# tsal.net
KiCad netlist of a schematic drawn in Altium Designer
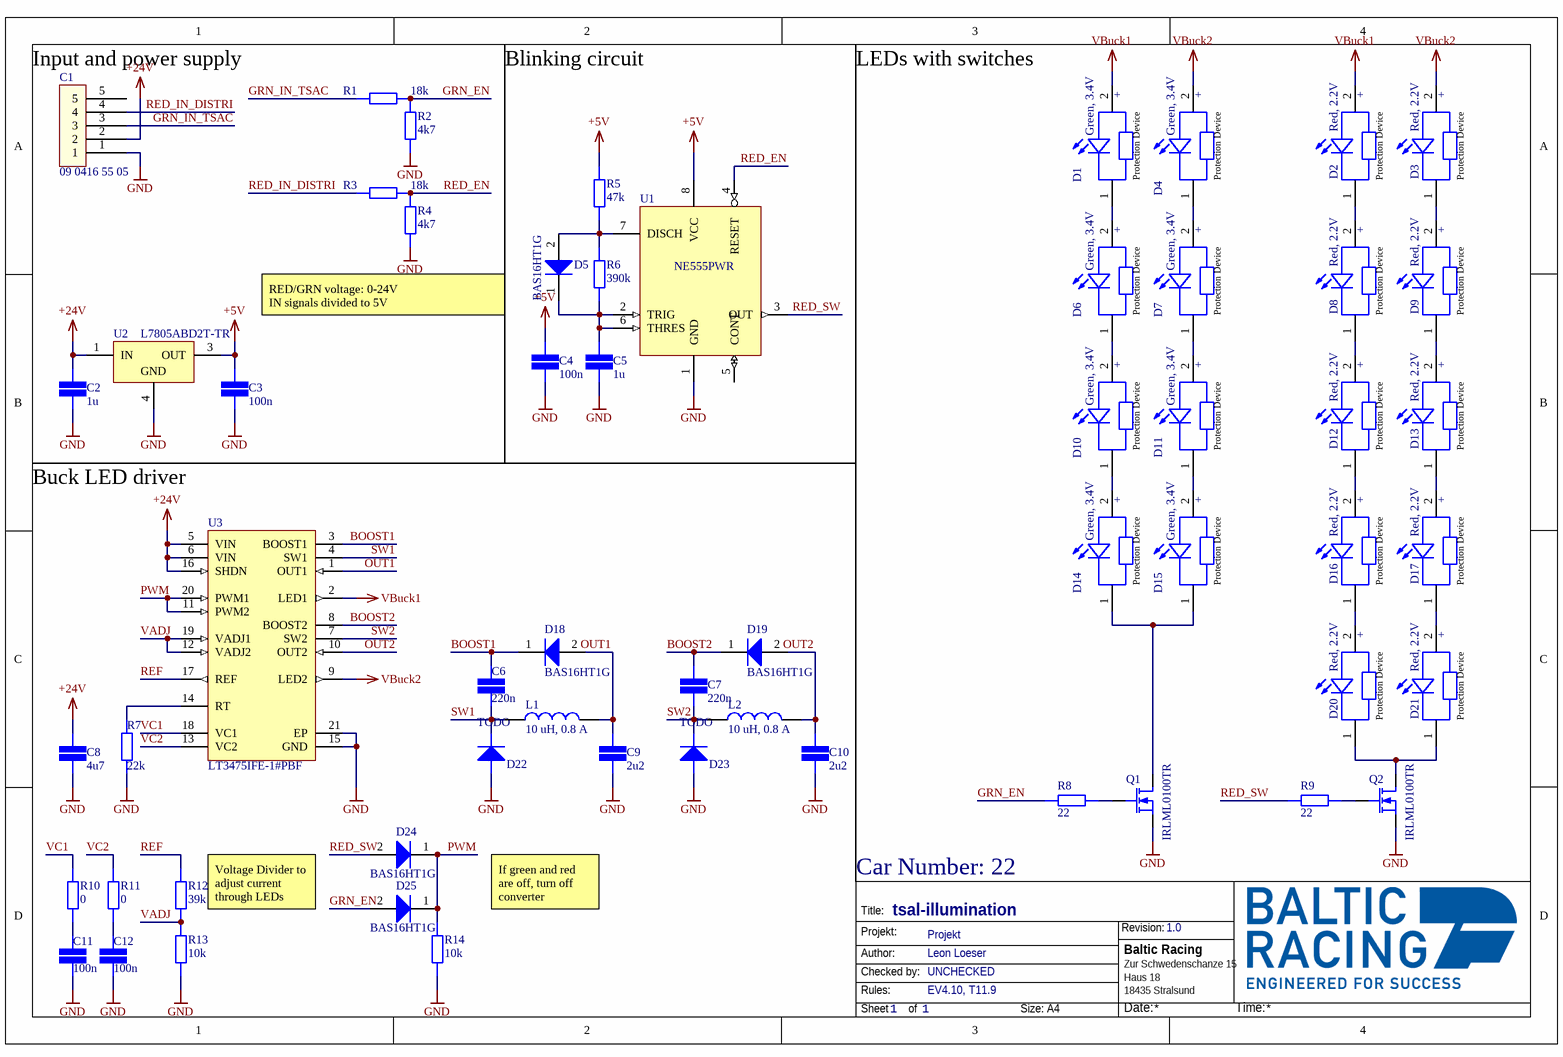
[diagram p0: tsal.SchDoc]

(export (version "E")
  (design (tool "Eeschema 10.0.6"))
  (components
    (comp (ref "C1")
      (value "09 0416 55 05")
      (footprint "BINDER_09_0416_30_05")
      (description "Binder 5 Pin Female SnapIn 90°")
      (libsource (lib "Leon") (part "09 0416 55 05"))
    )
    (comp (ref "C2")
      (value "1u")
      (footprint "CAP 0805/2012")
      (description "Capacitor with multiple Footprints")
      (fields (field (name "VOLTAGE") "25V") (field (name "Comment") "SMD Capacitor"))
      (libsource (lib "Standardbauteile") (part "SMD Capacitor"))
    )
    (comp (ref "C3")
      (value "100n")
      (footprint "CAP 0603/1608")
      (description "Capacitor with multiple Footprints")
      (fields (field (name "VOLTAGE") "6.3V") (field (name "Comment") "SMD Capacitor"))
      (libsource (lib "Standardbauteile") (part "SMD Capacitor"))
    )
    (comp (ref "C4")
      (value "100n")
      (footprint "CAP 0603/1608")
      (description "Capacitor with multiple Footprints")
      (fields (field (name "VOLTAGE") "6.3V") (field (name "Comment") "SMD Capacitor"))
      (libsource (lib "Standardbauteile") (part "SMD Capacitor"))
    )
    (comp (ref "C5")
      (value "1u")
      (footprint "CAP 0805/2012")
      (description "Capacitor with multiple Footprints")
      (fields (field (name "VOLTAGE") "6.3V") (field (name "Comment") "SMD Capacitor"))
      (libsource (lib "") (part "SMD Capacitor_1"))
    )
    (comp (ref "C6")
      (value "220n")
      (footprint "CAP 0603/1608")
      (description "Capacitor with multiple Footprints")
      (fields (field (name "VOLTAGE") "25V") (field (name "Comment") "SMD Capacitor"))
      (libsource (lib "Standardbauteile") (part "SMD Capacitor"))
    )
    (comp (ref "C7")
      (value "220n")
      (footprint "CAP 0603/1608")
      (description "Capacitor with multiple Footprints")
      (fields (field (name "VOLTAGE") "25V") (field (name "Comment") "SMD Capacitor"))
      (libsource (lib "Standardbauteile") (part "SMD Capacitor"))
    )
    (comp (ref "C8")
      (value "4u7")
      (footprint "CAP 1206/3216")
      (description "Capacitor with multiple Footprints")
      (fields (field (name "VOLTAGE") "25V") (field (name "Comment") "SMD Capacitor"))
      (libsource (lib "Standardbauteile") (part "SMD Capacitor"))
    )
    (comp (ref "C9")
      (value "2u2")
      (footprint "CAP 1206/3216")
      (description "Capacitor with multiple Footprints")
      (fields (field (name "VOLTAGE") "25V") (field (name "Comment") "SMD Capacitor"))
      (libsource (lib "Standardbauteile") (part "SMD Capacitor"))
    )
    (comp (ref "C10")
      (value "2u2")
      (footprint "CAP 1206/3216")
      (description "Capacitor with multiple Footprints")
      (fields (field (name "VOLTAGE") "25V") (field (name "Comment") "SMD Capacitor"))
      (libsource (lib "Standardbauteile") (part "SMD Capacitor"))
    )
    (comp (ref "C11")
      (value "100n")
      (footprint "CAP 0603/1608")
      (description "Capacitor with multiple Footprints")
      (fields (field (name "VOLTAGE") "25V") (field (name "Comment") "SMD Capacitor"))
      (libsource (lib "Standardbauteile") (part "SMD Capacitor"))
    )
    (comp (ref "C12")
      (value "100n")
      (footprint "CAP 0603/1608")
      (description "Capacitor with multiple Footprints")
      (fields (field (name "VOLTAGE") "25V") (field (name "Comment") "SMD Capacitor"))
      (libsource (lib "Standardbauteile") (part "SMD Capacitor"))
    )
    (comp (ref "D1")
      (value "Green, 3.4V")
      (footprint "WL-SMDC_3535")
      (description "WL-SMDC SMT Mono-color Ceramic LED Waterclear, size 3535, 3.4V, Green")
      (fields
        (field (name "MANUFACTURER PART NUMBER") "150353GS74500")
        (field (name "MANUFACTURER") "Wurth Elektronik")
      )
      (libsource (lib "Altium_WL-SMDC (rev20a)") (part "150353GS74500"))
    )
    (comp (ref "D2")
      (value "Red, 2.2V")
      (footprint "WL-SMDC_3535")
      (description "WL-SMDC SMT Mono-color Ceramic LED Waterclear, size 3535, 2.2V, Red")
      (fields
        (field (name "MANUFACTURER PART NUMBER") "150353RS74500")
        (field (name "MANUFACTURER") "Wurth Elektronik")
      )
      (libsource (lib "Altium_WL-SMDC (rev20a)") (part "150353RS74500"))
    )
    (comp (ref "D3")
      (value "Red, 2.2V")
      (footprint "WL-SMDC_3535")
      (description "WL-SMDC SMT Mono-color Ceramic LED Waterclear, size 3535, 2.2V, Red")
      (fields
        (field (name "MANUFACTURER PART NUMBER") "150353RS74500")
        (field (name "MANUFACTURER") "Wurth Elektronik")
      )
      (libsource (lib "Altium_WL-SMDC (rev20a)") (part "150353RS74500"))
    )
    (comp (ref "D4")
      (value "Green, 3.4V")
      (footprint "WL-SMDC_3535")
      (description "WL-SMDC SMT Mono-color Ceramic LED Waterclear, size 3535, 3.4V, Green")
      (fields
        (field (name "MANUFACTURER PART NUMBER") "150353GS74500")
        (field (name "MANUFACTURER") "Wurth Elektronik")
      )
      (libsource (lib "Altium_WL-SMDC (rev20a)") (part "150353GS74500"))
    )
    (comp (ref "D5")
      (value "BAS16HT1G")
      (footprint "ONSC-SOD-323-2-477-02_V")
      (description "Switching Diode, 2-Pin SOD-323, Pb-Free, Tape and Reel")
      (fields (field (name "MANUFACTURER") "On Semiconductor"))
      (libsource (lib "Altium Content Vault") (part "ONSC-D-K1A2-2"))
    )
    (comp (ref "D6")
      (value "Green, 3.4V")
      (footprint "WL-SMDC_3535")
      (description "WL-SMDC SMT Mono-color Ceramic LED Waterclear, size 3535, 3.4V, Green")
      (fields
        (field (name "MANUFACTURER PART NUMBER") "150353GS74500")
        (field (name "MANUFACTURER") "Wurth Elektronik")
      )
      (libsource (lib "Altium_WL-SMDC (rev20a)") (part "150353GS74500"))
    )
    (comp (ref "D7")
      (value "Green, 3.4V")
      (footprint "WL-SMDC_3535")
      (description "WL-SMDC SMT Mono-color Ceramic LED Waterclear, size 3535, 3.4V, Green")
      (fields
        (field (name "MANUFACTURER PART NUMBER") "150353GS74500")
        (field (name "MANUFACTURER") "Wurth Elektronik")
      )
      (libsource (lib "Altium_WL-SMDC (rev20a)") (part "150353GS74500"))
    )
    (comp (ref "D8")
      (value "Red, 2.2V")
      (footprint "WL-SMDC_3535")
      (description "WL-SMDC SMT Mono-color Ceramic LED Waterclear, size 3535, 2.2V, Red")
      (fields
        (field (name "MANUFACTURER PART NUMBER") "150353RS74500")
        (field (name "MANUFACTURER") "Wurth Elektronik")
      )
      (libsource (lib "Altium_WL-SMDC (rev20a)") (part "150353RS74500"))
    )
    (comp (ref "D9")
      (value "Red, 2.2V")
      (footprint "WL-SMDC_3535")
      (description "WL-SMDC SMT Mono-color Ceramic LED Waterclear, size 3535, 2.2V, Red")
      (fields
        (field (name "MANUFACTURER PART NUMBER") "150353RS74500")
        (field (name "MANUFACTURER") "Wurth Elektronik")
      )
      (libsource (lib "Altium_WL-SMDC (rev20a)") (part "150353RS74500"))
    )
    (comp (ref "D10")
      (value "Green, 3.4V")
      (footprint "WL-SMDC_3535")
      (description "WL-SMDC SMT Mono-color Ceramic LED Waterclear, size 3535, 3.4V, Green")
      (fields
        (field (name "MANUFACTURER PART NUMBER") "150353GS74500")
        (field (name "MANUFACTURER") "Wurth Elektronik")
      )
      (libsource (lib "Altium_WL-SMDC (rev20a)") (part "150353GS74500"))
    )
    (comp (ref "D11")
      (value "Green, 3.4V")
      (footprint "WL-SMDC_3535")
      (description "WL-SMDC SMT Mono-color Ceramic LED Waterclear, size 3535, 3.4V, Green")
      (fields
        (field (name "MANUFACTURER PART NUMBER") "150353GS74500")
        (field (name "MANUFACTURER") "Wurth Elektronik")
      )
      (libsource (lib "Altium_WL-SMDC (rev20a)") (part "150353GS74500"))
    )
    (comp (ref "D12")
      (value "Red, 2.2V")
      (footprint "WL-SMDC_3535")
      (description "WL-SMDC SMT Mono-color Ceramic LED Waterclear, size 3535, 2.2V, Red")
      (fields
        (field (name "MANUFACTURER PART NUMBER") "150353RS74500")
        (field (name "MANUFACTURER") "Wurth Elektronik")
      )
      (libsource (lib "Altium_WL-SMDC (rev20a)") (part "150353RS74500"))
    )
    (comp (ref "D13")
      (value "Red, 2.2V")
      (footprint "WL-SMDC_3535")
      (description "WL-SMDC SMT Mono-color Ceramic LED Waterclear, size 3535, 2.2V, Red")
      (fields
        (field (name "MANUFACTURER PART NUMBER") "150353RS74500")
        (field (name "MANUFACTURER") "Wurth Elektronik")
      )
      (libsource (lib "Altium_WL-SMDC (rev20a)") (part "150353RS74500"))
    )
    (comp (ref "D14")
      (value "Green, 3.4V")
      (footprint "WL-SMDC_3535")
      (description "WL-SMDC SMT Mono-color Ceramic LED Waterclear, size 3535, 3.4V, Green")
      (fields
        (field (name "MANUFACTURER PART NUMBER") "150353GS74500")
        (field (name "MANUFACTURER") "Wurth Elektronik")
      )
      (libsource (lib "Altium_WL-SMDC (rev20a)") (part "150353GS74500"))
    )
    (comp (ref "D15")
      (value "Green, 3.4V")
      (footprint "WL-SMDC_3535")
      (description "WL-SMDC SMT Mono-color Ceramic LED Waterclear, size 3535, 3.4V, Green")
      (fields
        (field (name "MANUFACTURER PART NUMBER") "150353GS74500")
        (field (name "MANUFACTURER") "Wurth Elektronik")
      )
      (libsource (lib "Altium_WL-SMDC (rev20a)") (part "150353GS74500"))
    )
    (comp (ref "D16")
      (value "Red, 2.2V")
      (footprint "WL-SMDC_3535")
      (description "WL-SMDC SMT Mono-color Ceramic LED Waterclear, size 3535, 2.2V, Red")
      (fields
        (field (name "MANUFACTURER PART NUMBER") "150353RS74500")
        (field (name "MANUFACTURER") "Wurth Elektronik")
      )
      (libsource (lib "Altium_WL-SMDC (rev20a)") (part "150353RS74500"))
    )
    (comp (ref "D17")
      (value "Red, 2.2V")
      (footprint "WL-SMDC_3535")
      (description "WL-SMDC SMT Mono-color Ceramic LED Waterclear, size 3535, 2.2V, Red")
      (fields
        (field (name "MANUFACTURER PART NUMBER") "150353RS74500")
        (field (name "MANUFACTURER") "Wurth Elektronik")
      )
      (libsource (lib "Altium_WL-SMDC (rev20a)") (part "150353RS74500"))
    )
    (comp (ref "D18")
      (value "BAS16HT1G")
      (footprint "ONSC-SOD-323-2-477-02_V")
      (description "Switching Diode, 2-Pin SOD-323, Pb-Free, Tape and Reel")
      (fields (field (name "MANUFACTURER") "On Semiconductor"))
      (libsource (lib "Altium Content Vault") (part "ONSC-D-K1A2-2"))
    )
    (comp (ref "D19")
      (value "BAS16HT1G")
      (footprint "ONSC-SOD-323-2-477-02_V")
      (description "Switching Diode, 2-Pin SOD-323, Pb-Free, Tape and Reel")
      (fields (field (name "MANUFACTURER") "On Semiconductor"))
      (libsource (lib "Altium Content Vault") (part "ONSC-D-K1A2-2"))
    )
    (comp (ref "D20")
      (value "Red, 2.2V")
      (footprint "WL-SMDC_3535")
      (description "WL-SMDC SMT Mono-color Ceramic LED Waterclear, size 3535, 2.2V, Red")
      (fields
        (field (name "MANUFACTURER PART NUMBER") "150353RS74500")
        (field (name "MANUFACTURER") "Wurth Elektronik")
      )
      (libsource (lib "Altium_WL-SMDC (rev20a)") (part "150353RS74500"))
    )
    (comp (ref "D21")
      (value "Red, 2.2V")
      (footprint "WL-SMDC_3535")
      (description "WL-SMDC SMT Mono-color Ceramic LED Waterclear, size 3535, 2.2V, Red")
      (fields
        (field (name "MANUFACTURER PART NUMBER") "150353RS74500")
        (field (name "MANUFACTURER") "Wurth Elektronik")
      )
      (libsource (lib "Altium_WL-SMDC (rev20a)") (part "150353RS74500"))
    )
    (comp (ref "D22")
      (value "TODO")
      (footprint "SOD123F")
      (libsource (lib "Standardbauteile") (part "SMD Diode"))
    )
    (comp (ref "D23")
      (value "TODO")
      (footprint "SOD123F")
      (libsource (lib "Standardbauteile") (part "SMD Diode"))
    )
    (comp (ref "D24")
      (value "BAS16HT1G")
      (footprint "ONSC-SOD-323-2-477-02_V")
      (description "Switching Diode, 2-Pin SOD-323, Pb-Free, Tape and Reel")
      (fields (field (name "MANUFACTURER") "On Semiconductor"))
      (libsource (lib "Altium Content Vault") (part "ONSC-D-K1A2-2"))
    )
    (comp (ref "D25")
      (value "BAS16HT1G")
      (footprint "ONSC-SOD-323-2-477-02_V")
      (description "Switching Diode, 2-Pin SOD-323, Pb-Free, Tape and Reel")
      (fields (field (name "MANUFACTURER") "On Semiconductor"))
      (libsource (lib "Altium Content Vault") (part "ONSC-D-K1A2-2"))
    )
    (comp (ref "L1")
      (value "10 uH, 0.8 A")
      (footprint "WE-LQSH_2512")
      (description "SMT Semi-Shielded High Saturation Power Inductor WE-LQSH, size 2512, 10 uH, 0.8 A")
      (fields (field (name "PART NUMBER") "74405024100") (field (name "PUBLISHER") "Wurth Elektronik"))
      (libsource (lib "ALTIUM-WE-LQSH-rev18a") (part "74405024100"))
    )
    (comp (ref "L2")
      (value "10 uH, 0.8 A")
      (footprint "WE-LQSH_2512")
      (description "SMT Semi-Shielded High Saturation Power Inductor WE-LQSH, size 2512, 10 uH, 0.8 A")
      (fields (field (name "PART NUMBER") "74405024100") (field (name "PUBLISHER") "Wurth Elektronik"))
      (libsource (lib "ALTIUM-WE-LQSH-rev18a") (part "74405024100"))
    )
    (comp (ref "Q1")
      (value "IRLML0100TR")
      (footprint "SOT23")
      (description "N-Channel MOSFET")
      (libsource (lib "Standardbauteile") (part "MOSFET N"))
    )
    (comp (ref "Q2")
      (value "IRLML0100TR")
      (footprint "SOT23")
      (description "N-Channel MOSFET")
      (libsource (lib "Standardbauteile") (part "MOSFET N"))
    )
    (comp (ref "R1")
      (value "18k")
      (footprint "STACKPOLE CSR0603")
      (description "Resistor with multiple footprints")
      (fields (field (name "Comment") "SMD Resistor"))
      (libsource (lib "Standardbauteile") (part "SMD Resistor"))
    )
    (comp (ref "R2")
      (value "4k7")
      (footprint "STACKPOLE CSR0603")
      (description "Resistor with multiple footprints")
      (fields (field (name "Comment") "SMD Resistor"))
      (libsource (lib "Standardbauteile") (part "SMD Resistor"))
    )
    (comp (ref "R3")
      (value "18k")
      (footprint "STACKPOLE CSR0603")
      (description "Resistor with multiple footprints")
      (fields (field (name "Comment") "SMD Resistor"))
      (libsource (lib "Standardbauteile") (part "SMD Resistor"))
    )
    (comp (ref "R4")
      (value "4k7")
      (footprint "STACKPOLE CSR0603")
      (description "Resistor with multiple footprints")
      (fields (field (name "Comment") "SMD Resistor"))
      (libsource (lib "Standardbauteile") (part "SMD Resistor"))
    )
    (comp (ref "R5")
      (value "47k")
      (footprint "STACKPOLE CSR0603")
      (description "Resistor with multiple footprints")
      (fields (field (name "Comment") "SMD Resistor"))
      (libsource (lib "Standardbauteile") (part "SMD Resistor"))
    )
    (comp (ref "R6")
      (value "390k")
      (footprint "STACKPOLE CSR0603")
      (description "Resistor with multiple footprints")
      (fields (field (name "Comment") "SMD Resistor"))
      (libsource (lib "Standardbauteile") (part "SMD Resistor"))
    )
    (comp (ref "R7")
      (value "22k")
      (footprint "STACKPOLE CSR0603")
      (description "Resistor with multiple footprints")
      (fields (field (name "Comment") "SMD Resistor"))
      (libsource (lib "Standardbauteile") (part "SMD Resistor"))
    )
    (comp (ref "R8")
      (value "22")
      (footprint "STACKPOLE CSR0603")
      (description "Resistor with multiple footprints")
      (fields (field (name "Comment") "SMD Resistor"))
      (libsource (lib "Standardbauteile") (part "SMD Resistor"))
    )
    (comp (ref "R9")
      (value "22")
      (footprint "STACKPOLE CSR0603")
      (description "Resistor with multiple footprints")
      (fields (field (name "Comment") "SMD Resistor"))
      (libsource (lib "Standardbauteile") (part "SMD Resistor"))
    )
    (comp (ref "R10")
      (value "0")
      (footprint "STACKPOLE CSR0603")
      (description "Resistor with multiple footprints")
      (fields (field (name "Comment") "SMD Resistor"))
      (libsource (lib "Standardbauteile") (part "SMD Resistor"))
    )
    (comp (ref "R11")
      (value "0")
      (footprint "STACKPOLE CSR0603")
      (description "Resistor with multiple footprints")
      (fields (field (name "Comment") "SMD Resistor"))
      (libsource (lib "Standardbauteile") (part "SMD Resistor"))
    )
    (comp (ref "R12")
      (value "39k")
      (footprint "STACKPOLE CSR0603")
      (description "Resistor with multiple footprints")
      (fields (field (name "Comment") "SMD Resistor"))
      (libsource (lib "Standardbauteile") (part "SMD Resistor"))
    )
    (comp (ref "R13")
      (value "10k")
      (footprint "STACKPOLE CSR0603")
      (description "Resistor with multiple footprints")
      (fields (field (name "Comment") "SMD Resistor"))
      (libsource (lib "Standardbauteile") (part "SMD Resistor"))
    )
    (comp (ref "R14")
      (value "10k")
      (footprint "STACKPOLE CSR0603")
      (description "Resistor with multiple footprints")
      (fields (field (name "Comment") "SMD Resistor"))
      (libsource (lib "Standardbauteile") (part "SMD Resistor"))
    )
    (comp (ref "U1")
      (value "NE555PWR")
      (footprint "8-TSSOP")
      (libsource (lib "Standardbauteile") (part "NE555"))
    )
    (comp (ref "U2")
      (value "L7805ABD2T-TR")
      (footprint "TO-263_M")
      (description "Positive Voltage Regulator, 3-Pin D2PAK, Tape and Reel")
      (libsource (lib "Altium Content Vault") (part "PM-REG-L4940-SOT3"))
    )
    (comp (ref "U3")
      (value "LT3475IFE-1#PBF")
      (footprint "LT-FE-20-EPV-CB_L")
      (fields (field (name "MANUFACTURER") "Linear Technology"))
      (libsource (lib "Altium Content Vault") (part "LT-LT3475-X-FE-20"))
    )
  )
  (nets
    (net (code "1") (name "+5V") (class "Default")
      (node (ref "C3") (pin "2") (pinfunction "2_2") (pintype "passive"))
      (node (ref "C4") (pin "2") (pinfunction "2_2") (pintype "passive"))
      (node (ref "R5") (pin "2") (pinfunction "2_2") (pintype "passive"))
      (node (ref "U1") (pin "8") (pinfunction "VCC_8") (pintype "power_in"))
      (node (ref "U2") (pin "3") (pinfunction "OUT_3") (pintype "power_in"))
    )
    (net (code "2") (name "+24V") (class "Default")
      (node (ref "C1") (pin "2") (pinfunction "2_2") (pintype "passive"))
      (node (ref "C2") (pin "2") (pinfunction "2_2") (pintype "passive"))
      (node (ref "C8") (pin "2") (pinfunction "2_2") (pintype "passive"))
      (node (ref "U2") (pin "1") (pinfunction "IN_1") (pintype "power_in"))
      (node (ref "U3") (pin "16") (pinfunction "SHDN_16") (pintype "input"))
      (node (ref "U3") (pin "5") (pinfunction "VIN_5") (pintype "power_in"))
      (node (ref "U3") (pin "6") (pinfunction "VIN_6") (pintype "power_in"))
    )
    (net (code "3") (name "/BOOST1") (class "Default")
      (node (ref "C6") (pin "2") (pinfunction "2_2") (pintype "passive"))
      (node (ref "D18") (pin "1") (pinfunction "K_1") (pintype "passive"))
      (node (ref "U3") (pin "3") (pinfunction "BOOST1_3") (pintype "passive"))
    )
    (net (code "4") (name "/BOOST2") (class "Default")
      (node (ref "C7") (pin "2") (pinfunction "2_2") (pintype "passive"))
      (node (ref "D19") (pin "1") (pinfunction "K_1") (pintype "passive"))
      (node (ref "U3") (pin "8") (pinfunction "BOOST2_8") (pintype "passive"))
    )
    (net (code "5") (name "/GRN_EN") (class "Default")
      (node (ref "D25") (pin "2") (pinfunction "A_2") (pintype "passive"))
      (node (ref "R1") (pin "2") (pinfunction "2_2") (pintype "passive"))
      (node (ref "R2") (pin "2") (pinfunction "2_2") (pintype "passive"))
      (node (ref "R8") (pin "2") (pinfunction "2_2") (pintype "passive"))
    )
    (net (code "6") (name "/GRN_IN_TSAC") (class "Default")
      (node (ref "C1") (pin "3") (pinfunction "3_3") (pintype "passive"))
      (node (ref "R1") (pin "1") (pinfunction "1_1") (pintype "passive"))
    )
    (net (code "7") (name "/OUT1") (class "Default")
      (node (ref "C9") (pin "2") (pinfunction "2_2") (pintype "passive"))
      (node (ref "D18") (pin "2") (pinfunction "A_2") (pintype "passive"))
      (node (ref "L1") (pin "2") (pinfunction "2_2") (pintype "passive"))
      (node (ref "U3") (pin "1") (pinfunction "OUT1_1") (pintype "input"))
    )
    (net (code "8") (name "/OUT2") (class "Default")
      (node (ref "C10") (pin "2") (pinfunction "2_2") (pintype "passive"))
      (node (ref "D19") (pin "2") (pinfunction "A_2") (pintype "passive"))
      (node (ref "L2") (pin "2") (pinfunction "2_2") (pintype "passive"))
      (node (ref "U3") (pin "10") (pinfunction "OUT2_10") (pintype "input"))
    )
    (net (code "9") (name "/PWM") (class "Default")
      (node (ref "D24") (pin "1") (pinfunction "K_1") (pintype "passive"))
      (node (ref "D25") (pin "1") (pinfunction "K_1") (pintype "passive"))
      (node (ref "R14") (pin "1") (pinfunction "1_1") (pintype "passive"))
      (node (ref "U3") (pin "11") (pinfunction "PWM2_11") (pintype "input"))
      (node (ref "U3") (pin "20") (pinfunction "PWM1_20") (pintype "input"))
    )
    (net (code "10") (name "/RED_EN") (class "Default")
      (node (ref "R3") (pin "2") (pinfunction "2_2") (pintype "passive"))
      (node (ref "R4") (pin "2") (pinfunction "2_2") (pintype "passive"))
      (node (ref "U1") (pin "4") (pinfunction "RESET_4") (pintype "input"))
    )
    (net (code "11") (name "/RED_IN_DISTRI") (class "Default")
      (node (ref "C1") (pin "4") (pinfunction "4_4") (pintype "passive"))
      (node (ref "R3") (pin "1") (pinfunction "1_1") (pintype "passive"))
    )
    (net (code "12") (name "/RED_SW") (class "Default")
      (node (ref "D24") (pin "2") (pinfunction "A_2") (pintype "passive"))
      (node (ref "R9") (pin "2") (pinfunction "2_2") (pintype "passive"))
      (node (ref "U1") (pin "3") (pinfunction "OUT_3") (pintype "output"))
    )
    (net (code "13") (name "/REF") (class "Default")
      (node (ref "R12") (pin "1") (pinfunction "1_1") (pintype "passive"))
      (node (ref "U3") (pin "17") (pinfunction "REF_17") (pintype "output"))
    )
    (net (code "14") (name "/SW1") (class "Default")
      (node (ref "C6") (pin "1") (pinfunction "1_1") (pintype "passive"))
      (node (ref "D22") (pin "C") (pinfunction "C_C") (pintype "passive"))
      (node (ref "L1") (pin "1") (pinfunction "1_1") (pintype "passive"))
      (node (ref "U3") (pin "4") (pinfunction "SW1_4") (pintype "passive"))
    )
    (net (code "15") (name "/SW2") (class "Default")
      (node (ref "C7") (pin "1") (pinfunction "1_1") (pintype "passive"))
      (node (ref "D23") (pin "C") (pinfunction "C_C") (pintype "passive"))
      (node (ref "L2") (pin "1") (pinfunction "1_1") (pintype "passive"))
      (node (ref "U3") (pin "7") (pinfunction "SW2_7") (pintype "passive"))
    )
    (net (code "16") (name "/VADJ") (class "Default")
      (node (ref "R12") (pin "2") (pinfunction "2_2") (pintype "passive"))
      (node (ref "R13") (pin "1") (pinfunction "1_1") (pintype "passive"))
      (node (ref "U3") (pin "12") (pinfunction "VADJ2_12") (pintype "input"))
      (node (ref "U3") (pin "19") (pinfunction "VADJ1_19") (pintype "input"))
    )
    (net (code "17") (name "/VC1") (class "Default")
      (node (ref "R10") (pin "1") (pinfunction "1_1") (pintype "passive"))
      (node (ref "U3") (pin "18") (pinfunction "VC1_18") (pintype "passive"))
    )
    (net (code "18") (name "/VC2") (class "Default")
      (node (ref "R11") (pin "1") (pinfunction "1_1") (pintype "passive"))
      (node (ref "U3") (pin "13") (pinfunction "VC2_13") (pintype "passive"))
    )
    (net (code "19") (name "GND") (class "Default")
      (node (ref "C1") (pin "1") (pinfunction "1_1") (pintype "passive"))
      (node (ref "C10") (pin "1") (pinfunction "1_1") (pintype "passive"))
      (node (ref "C11") (pin "1") (pinfunction "1_1") (pintype "passive"))
      (node (ref "C12") (pin "1") (pinfunction "1_1") (pintype "passive"))
      (node (ref "C2") (pin "1") (pinfunction "1_1") (pintype "passive"))
      (node (ref "C3") (pin "1") (pinfunction "1_1") (pintype "passive"))
      (node (ref "C4") (pin "1") (pinfunction "1_1") (pintype "passive"))
      (node (ref "C5") (pin "2") (pinfunction "2_2") (pintype "passive"))
      (node (ref "C8") (pin "1") (pinfunction "1_1") (pintype "passive"))
      (node (ref "C9") (pin "1") (pinfunction "1_1") (pintype "passive"))
      (node (ref "D22") (pin "A") (pinfunction "A_A") (pintype "passive"))
      (node (ref "D23") (pin "A") (pinfunction "A_A") (pintype "passive"))
      (node (ref "Q1") (pin "2") (pinfunction "S_2") (pintype "passive"))
      (node (ref "Q2") (pin "2") (pinfunction "S_2") (pintype "passive"))
      (node (ref "R13") (pin "2") (pinfunction "2_2") (pintype "passive"))
      (node (ref "R14") (pin "2") (pinfunction "2_2") (pintype "passive"))
      (node (ref "R2") (pin "1") (pinfunction "1_1") (pintype "passive"))
      (node (ref "R4") (pin "1") (pinfunction "1_1") (pintype "passive"))
      (node (ref "R7") (pin "2") (pinfunction "2_2") (pintype "passive"))
      (node (ref "U1") (pin "1") (pinfunction "GND_1") (pintype "power_in"))
      (node (ref "U2") (pin "4") (pinfunction "GND_4") (pintype "power_in"))
      (node (ref "U3") (pin "15") (pinfunction "GND_15") (pintype "power_in"))
      (node (ref "U3") (pin "21") (pinfunction "EP_21") (pintype "power_in"))
    )
    (net (code "20") (name "Net-(C11-Pad2)") (class "Default")
      (node (ref "C11") (pin "2") (pinfunction "2_2") (pintype "passive"))
      (node (ref "R10") (pin "2") (pinfunction "2_2") (pintype "passive"))
    )
    (net (code "21") (name "Net-(C12-Pad2)") (class "Default")
      (node (ref "C12") (pin "2") (pinfunction "2_2") (pintype "passive"))
      (node (ref "R11") (pin "2") (pinfunction "2_2") (pintype "passive"))
    )
    (net (code "22") (name "Net-(D1-K)") (class "Default")
      (node (ref "D1") (pin "1") (pinfunction "K_1") (pintype "passive"))
      (node (ref "D6") (pin "2") (pinfunction "A_2") (pintype "passive"))
    )
    (net (code "23") (name "Net-(D2-K)") (class "Default")
      (node (ref "D2") (pin "1") (pinfunction "K_1") (pintype "passive"))
      (node (ref "D8") (pin "2") (pinfunction "A_2") (pintype "passive"))
    )
    (net (code "24") (name "Net-(D3-K)") (class "Default")
      (node (ref "D3") (pin "1") (pinfunction "K_1") (pintype "passive"))
      (node (ref "D9") (pin "2") (pinfunction "A_2") (pintype "passive"))
    )
    (net (code "25") (name "Net-(D4-K)") (class "Default")
      (node (ref "D4") (pin "1") (pinfunction "K_1") (pintype "passive"))
      (node (ref "D7") (pin "2") (pinfunction "A_2") (pintype "passive"))
    )
    (net (code "26") (name "Net-(D5-A)") (class "Default")
      (node (ref "D5") (pin "2") (pinfunction "A_2") (pintype "passive"))
      (node (ref "R5") (pin "1") (pinfunction "1_1") (pintype "passive"))
      (node (ref "R6") (pin "2") (pinfunction "2_2") (pintype "passive"))
      (node (ref "U1") (pin "7") (pinfunction "DISCH_7") (pintype "open_collector"))
    )
    (net (code "27") (name "Net-(D5-K)") (class "Default")
      (node (ref "C5") (pin "1") (pinfunction "1_1") (pintype "passive"))
      (node (ref "D5") (pin "1") (pinfunction "K_1") (pintype "passive"))
      (node (ref "R6") (pin "1") (pinfunction "1_1") (pintype "passive"))
      (node (ref "U1") (pin "2") (pinfunction "TRIG_2") (pintype "input"))
      (node (ref "U1") (pin "6") (pinfunction "THRES_6") (pintype "input"))
    )
    (net (code "28") (name "Net-(D10-A)") (class "Default")
      (node (ref "D10") (pin "2") (pinfunction "A_2") (pintype "passive"))
      (node (ref "D6") (pin "1") (pinfunction "K_1") (pintype "passive"))
    )
    (net (code "29") (name "Net-(D10-K)") (class "Default")
      (node (ref "D10") (pin "1") (pinfunction "K_1") (pintype "passive"))
      (node (ref "D14") (pin "2") (pinfunction "A_2") (pintype "passive"))
    )
    (net (code "30") (name "Net-(D11-A)") (class "Default")
      (node (ref "D11") (pin "2") (pinfunction "A_2") (pintype "passive"))
      (node (ref "D7") (pin "1") (pinfunction "K_1") (pintype "passive"))
    )
    (net (code "31") (name "Net-(D11-K)") (class "Default")
      (node (ref "D11") (pin "1") (pinfunction "K_1") (pintype "passive"))
      (node (ref "D15") (pin "2") (pinfunction "A_2") (pintype "passive"))
    )
    (net (code "32") (name "Net-(D12-A)") (class "Default")
      (node (ref "D12") (pin "2") (pinfunction "A_2") (pintype "passive"))
      (node (ref "D8") (pin "1") (pinfunction "K_1") (pintype "passive"))
    )
    (net (code "33") (name "Net-(D12-K)") (class "Default")
      (node (ref "D12") (pin "1") (pinfunction "K_1") (pintype "passive"))
      (node (ref "D16") (pin "2") (pinfunction "A_2") (pintype "passive"))
    )
    (net (code "34") (name "Net-(D13-A)") (class "Default")
      (node (ref "D13") (pin "2") (pinfunction "A_2") (pintype "passive"))
      (node (ref "D9") (pin "1") (pinfunction "K_1") (pintype "passive"))
    )
    (net (code "35") (name "Net-(D13-K)") (class "Default")
      (node (ref "D13") (pin "1") (pinfunction "K_1") (pintype "passive"))
      (node (ref "D17") (pin "2") (pinfunction "A_2") (pintype "passive"))
    )
    (net (code "36") (name "Net-(D14-K)") (class "Default")
      (node (ref "D14") (pin "1") (pinfunction "K_1") (pintype "passive"))
      (node (ref "D15") (pin "1") (pinfunction "K_1") (pintype "passive"))
      (node (ref "Q1") (pin "3") (pinfunction "D_3") (pintype "passive"))
    )
    (net (code "37") (name "Net-(D16-K)") (class "Default")
      (node (ref "D16") (pin "1") (pinfunction "K_1") (pintype "passive"))
      (node (ref "D20") (pin "2") (pinfunction "A_2") (pintype "passive"))
    )
    (net (code "38") (name "Net-(D17-K)") (class "Default")
      (node (ref "D17") (pin "1") (pinfunction "K_1") (pintype "passive"))
      (node (ref "D21") (pin "2") (pinfunction "A_2") (pintype "passive"))
    )
    (net (code "39") (name "Net-(D20-K)") (class "Default")
      (node (ref "D20") (pin "1") (pinfunction "K_1") (pintype "passive"))
      (node (ref "D21") (pin "1") (pinfunction "K_1") (pintype "passive"))
      (node (ref "Q2") (pin "3") (pinfunction "D_3") (pintype "passive"))
    )
    (net (code "40") (name "Net-(Q1-G)") (class "Default")
      (node (ref "Q1") (pin "1") (pinfunction "G_1") (pintype "passive"))
      (node (ref "R8") (pin "1") (pinfunction "1_1") (pintype "passive"))
    )
    (net (code "41") (name "Net-(Q2-G)") (class "Default")
      (node (ref "Q2") (pin "1") (pinfunction "G_1") (pintype "passive"))
      (node (ref "R9") (pin "1") (pinfunction "1_1") (pintype "passive"))
    )
    (net (code "42") (name "Net-(U3-RT)") (class "Default")
      (node (ref "R7") (pin "1") (pinfunction "1_1") (pintype "passive"))
      (node (ref "U3") (pin "14") (pinfunction "RT_14") (pintype "passive"))
    )
    (net (code "43") (name "VBuck1") (class "Default")
      (node (ref "D1") (pin "2") (pinfunction "A_2") (pintype "passive"))
      (node (ref "D2") (pin "2") (pinfunction "A_2") (pintype "passive"))
      (node (ref "U3") (pin "2") (pinfunction "LED1_2") (pintype "output"))
    )
    (net (code "44") (name "VBuck2") (class "Default")
      (node (ref "D3") (pin "2") (pinfunction "A_2") (pintype "passive"))
      (node (ref "D4") (pin "2") (pinfunction "A_2") (pintype "passive"))
      (node (ref "U3") (pin "9") (pinfunction "LED2_9") (pintype "output"))
    )
    (net (code "45") (name "unconnected-(C1-Pad5)") (class "Default")
      (node (ref "C1") (pin "5") (pinfunction "5_5") (pintype "passive"))
    )
    (net (code "46") (name "unconnected-(U1-CONT-Pad5)") (class "Default")
      (node (ref "U1") (pin "5") (pinfunction "CONT_5") (pintype "bidirectional"))
    )
  )
)
